# poker_shematics_2.net
KiCad netlist of a schematic drawn in Altium Designer
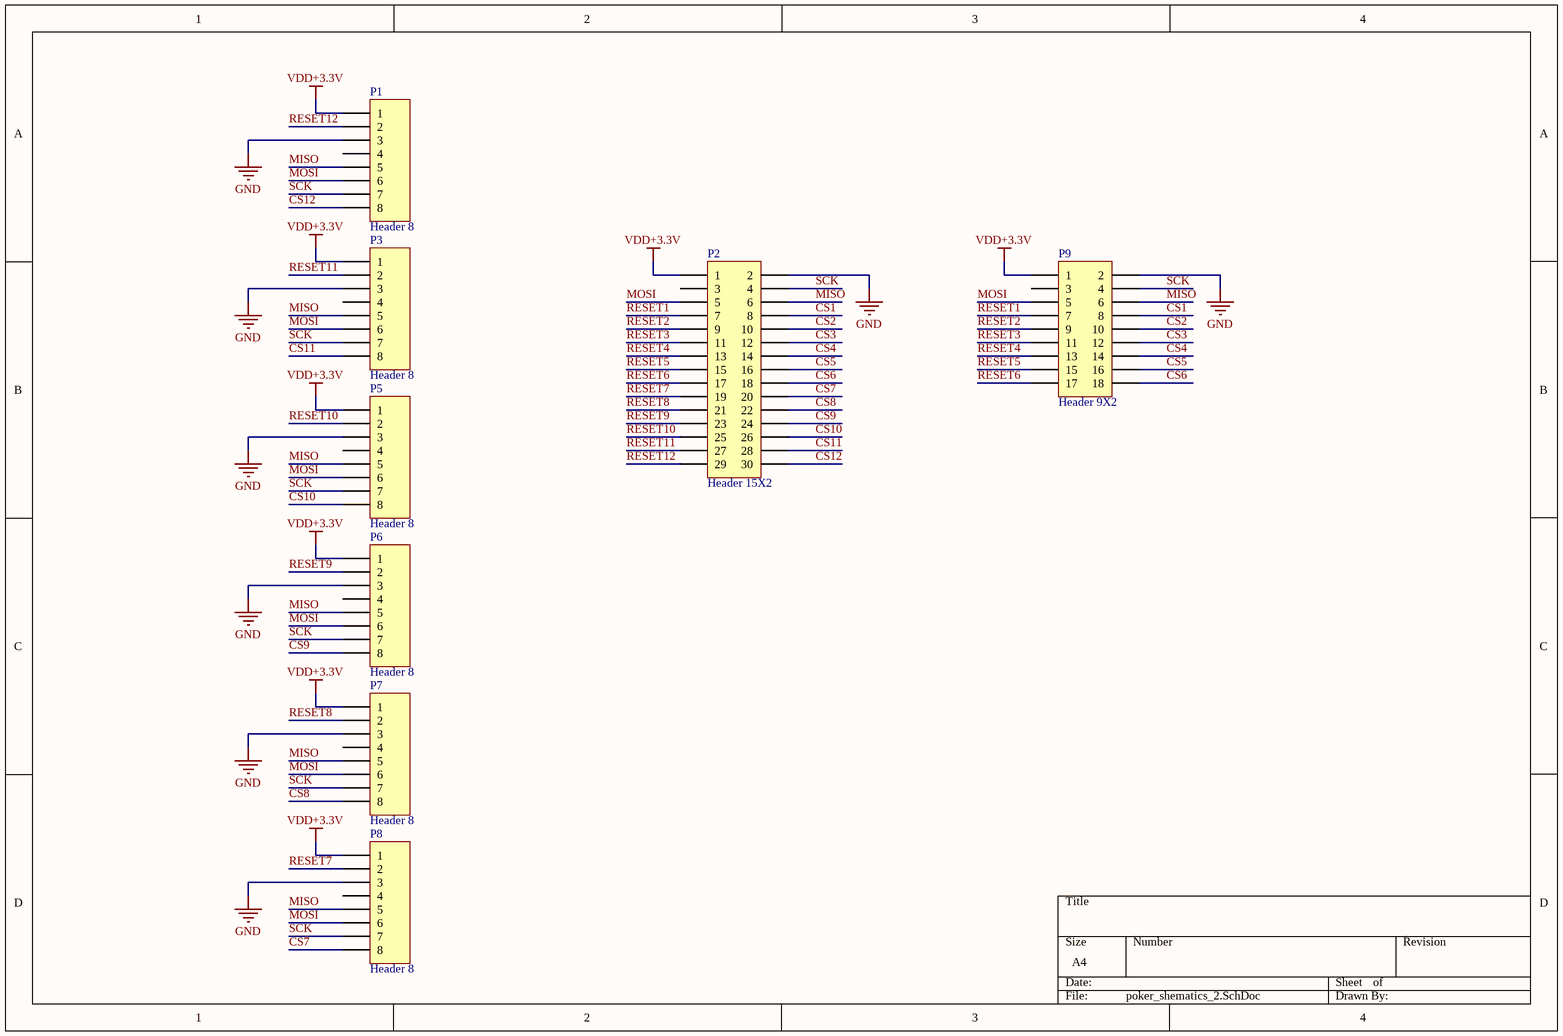
[diagram p0: poker_shematics_2.SchDoc]

(export (version "E")
  (design (tool "Eeschema 10.0.6"))
  (components
    (comp (ref "P1")
      (value "Header 8")
      (footprint "HDR1X8")
      (description "Header, 8-Pin")
      (fields (field (name "PUBLISHER") "Altium Limited"))
      (libsource (lib "Miscellaneous Connectors") (part "Header 8"))
    )
    (comp (ref "P2")
      (value "Header 15X2")
      (footprint "HDR2X15")
      (description "Header, 15-Pin, Dual row")
      (fields (field (name "PUBLISHER") "Altium Limited"))
      (libsource (lib "Miscellaneous Connectors") (part "Header 15X2"))
    )
    (comp (ref "P3")
      (value "Header 8")
      (footprint "HDR1X8")
      (description "Header, 8-Pin")
      (fields (field (name "PUBLISHER") "Altium Limited"))
      (libsource (lib "Miscellaneous Connectors") (part "Header 8"))
    )
    (comp (ref "P5")
      (value "Header 8")
      (footprint "HDR1X8")
      (description "Header, 8-Pin")
      (fields (field (name "PUBLISHER") "Altium Limited"))
      (libsource (lib "Miscellaneous Connectors") (part "Header 8"))
    )
    (comp (ref "P6")
      (value "Header 8")
      (footprint "HDR1X8")
      (description "Header, 8-Pin")
      (fields (field (name "PUBLISHER") "Altium Limited"))
      (libsource (lib "Miscellaneous Connectors") (part "Header 8"))
    )
    (comp (ref "P7")
      (value "Header 8")
      (footprint "HDR1X8")
      (description "Header, 8-Pin")
      (fields (field (name "PUBLISHER") "Altium Limited"))
      (libsource (lib "Miscellaneous Connectors") (part "Header 8"))
    )
    (comp (ref "P8")
      (value "Header 8")
      (footprint "HDR1X8")
      (description "Header, 8-Pin")
      (fields (field (name "PUBLISHER") "Altium Limited"))
      (libsource (lib "Miscellaneous Connectors") (part "Header 8"))
    )
    (comp (ref "P9")
      (value "Header 9X2")
      (footprint "HDR2X9")
      (description "Header, 9-Pin, Dual row")
      (fields (field (name "PUBLISHER") "Altium Limited"))
      (libsource (lib "Miscellaneous Connectors") (part "Header 9X2"))
    )
  )
  (nets
    (net (code "1") (name "/CS1") (class "Default")
      (node (ref "P2") (pin "8") (pinfunction "8_8") (pintype "passive"))
      (node (ref "P9") (pin "8") (pinfunction "8_8") (pintype "passive"))
    )
    (net (code "2") (name "/CS2") (class "Default")
      (node (ref "P2") (pin "10") (pinfunction "10_10") (pintype "passive"))
      (node (ref "P9") (pin "10") (pinfunction "10_10") (pintype "passive"))
    )
    (net (code "3") (name "/CS3") (class "Default")
      (node (ref "P2") (pin "12") (pinfunction "12_12") (pintype "passive"))
      (node (ref "P9") (pin "12") (pinfunction "12_12") (pintype "passive"))
    )
    (net (code "4") (name "/CS4") (class "Default")
      (node (ref "P2") (pin "14") (pinfunction "14_14") (pintype "passive"))
      (node (ref "P9") (pin "14") (pinfunction "14_14") (pintype "passive"))
    )
    (net (code "5") (name "/CS5") (class "Default")
      (node (ref "P2") (pin "16") (pinfunction "16_16") (pintype "passive"))
      (node (ref "P9") (pin "16") (pinfunction "16_16") (pintype "passive"))
    )
    (net (code "6") (name "/CS6") (class "Default")
      (node (ref "P2") (pin "18") (pinfunction "18_18") (pintype "passive"))
      (node (ref "P9") (pin "18") (pinfunction "18_18") (pintype "passive"))
    )
    (net (code "7") (name "/CS7") (class "Default")
      (node (ref "P2") (pin "20") (pinfunction "20_20") (pintype "passive"))
      (node (ref "P8") (pin "8") (pinfunction "8_8") (pintype "passive"))
    )
    (net (code "8") (name "/CS8") (class "Default")
      (node (ref "P2") (pin "22") (pinfunction "22_22") (pintype "passive"))
      (node (ref "P7") (pin "8") (pinfunction "8_8") (pintype "passive"))
    )
    (net (code "9") (name "/CS9") (class "Default")
      (node (ref "P2") (pin "24") (pinfunction "24_24") (pintype "passive"))
      (node (ref "P6") (pin "8") (pinfunction "8_8") (pintype "passive"))
    )
    (net (code "10") (name "/CS10") (class "Default")
      (node (ref "P2") (pin "26") (pinfunction "26_26") (pintype "passive"))
      (node (ref "P5") (pin "8") (pinfunction "8_8") (pintype "passive"))
    )
    (net (code "11") (name "/CS11") (class "Default")
      (node (ref "P2") (pin "28") (pinfunction "28_28") (pintype "passive"))
      (node (ref "P3") (pin "8") (pinfunction "8_8") (pintype "passive"))
    )
    (net (code "12") (name "/CS12") (class "Default")
      (node (ref "P1") (pin "8") (pinfunction "8_8") (pintype "passive"))
      (node (ref "P2") (pin "30") (pinfunction "30_30") (pintype "passive"))
    )
    (net (code "13") (name "/MISO") (class "Default")
      (node (ref "P1") (pin "5") (pinfunction "5_5") (pintype "passive"))
      (node (ref "P2") (pin "6") (pinfunction "6_6") (pintype "passive"))
      (node (ref "P3") (pin "5") (pinfunction "5_5") (pintype "passive"))
      (node (ref "P5") (pin "5") (pinfunction "5_5") (pintype "passive"))
      (node (ref "P6") (pin "5") (pinfunction "5_5") (pintype "passive"))
      (node (ref "P7") (pin "5") (pinfunction "5_5") (pintype "passive"))
      (node (ref "P8") (pin "5") (pinfunction "5_5") (pintype "passive"))
      (node (ref "P9") (pin "6") (pinfunction "6_6") (pintype "passive"))
    )
    (net (code "14") (name "/MOSI") (class "Default")
      (node (ref "P1") (pin "6") (pinfunction "6_6") (pintype "passive"))
      (node (ref "P2") (pin "5") (pinfunction "5_5") (pintype "passive"))
      (node (ref "P3") (pin "6") (pinfunction "6_6") (pintype "passive"))
      (node (ref "P5") (pin "6") (pinfunction "6_6") (pintype "passive"))
      (node (ref "P6") (pin "6") (pinfunction "6_6") (pintype "passive"))
      (node (ref "P7") (pin "6") (pinfunction "6_6") (pintype "passive"))
      (node (ref "P8") (pin "6") (pinfunction "6_6") (pintype "passive"))
      (node (ref "P9") (pin "5") (pinfunction "5_5") (pintype "passive"))
    )
    (net (code "15") (name "/RESET1") (class "Default")
      (node (ref "P2") (pin "7") (pinfunction "7_7") (pintype "passive"))
      (node (ref "P9") (pin "7") (pinfunction "7_7") (pintype "passive"))
    )
    (net (code "16") (name "/RESET2") (class "Default")
      (node (ref "P2") (pin "9") (pinfunction "9_9") (pintype "passive"))
      (node (ref "P9") (pin "9") (pinfunction "9_9") (pintype "passive"))
    )
    (net (code "17") (name "/RESET3") (class "Default")
      (node (ref "P2") (pin "11") (pinfunction "11_11") (pintype "passive"))
      (node (ref "P9") (pin "11") (pinfunction "11_11") (pintype "passive"))
    )
    (net (code "18") (name "/RESET4") (class "Default")
      (node (ref "P2") (pin "13") (pinfunction "13_13") (pintype "passive"))
      (node (ref "P9") (pin "13") (pinfunction "13_13") (pintype "passive"))
    )
    (net (code "19") (name "/RESET5") (class "Default")
      (node (ref "P2") (pin "15") (pinfunction "15_15") (pintype "passive"))
      (node (ref "P9") (pin "15") (pinfunction "15_15") (pintype "passive"))
    )
    (net (code "20") (name "/RESET6") (class "Default")
      (node (ref "P2") (pin "17") (pinfunction "17_17") (pintype "passive"))
      (node (ref "P9") (pin "17") (pinfunction "17_17") (pintype "passive"))
    )
    (net (code "21") (name "/RESET7") (class "Default")
      (node (ref "P2") (pin "19") (pinfunction "19_19") (pintype "passive"))
      (node (ref "P8") (pin "2") (pinfunction "2_2") (pintype "passive"))
    )
    (net (code "22") (name "/RESET8") (class "Default")
      (node (ref "P2") (pin "21") (pinfunction "21_21") (pintype "passive"))
      (node (ref "P7") (pin "2") (pinfunction "2_2") (pintype "passive"))
    )
    (net (code "23") (name "/RESET9") (class "Default")
      (node (ref "P2") (pin "23") (pinfunction "23_23") (pintype "passive"))
      (node (ref "P6") (pin "2") (pinfunction "2_2") (pintype "passive"))
    )
    (net (code "24") (name "/RESET10") (class "Default")
      (node (ref "P2") (pin "25") (pinfunction "25_25") (pintype "passive"))
      (node (ref "P5") (pin "2") (pinfunction "2_2") (pintype "passive"))
    )
    (net (code "25") (name "/RESET11") (class "Default")
      (node (ref "P2") (pin "27") (pinfunction "27_27") (pintype "passive"))
      (node (ref "P3") (pin "2") (pinfunction "2_2") (pintype "passive"))
    )
    (net (code "26") (name "/RESET12") (class "Default")
      (node (ref "P1") (pin "2") (pinfunction "2_2") (pintype "passive"))
      (node (ref "P2") (pin "29") (pinfunction "29_29") (pintype "passive"))
    )
    (net (code "27") (name "/SCK") (class "Default")
      (node (ref "P1") (pin "7") (pinfunction "7_7") (pintype "passive"))
      (node (ref "P2") (pin "4") (pinfunction "4_4") (pintype "passive"))
      (node (ref "P3") (pin "7") (pinfunction "7_7") (pintype "passive"))
      (node (ref "P5") (pin "7") (pinfunction "7_7") (pintype "passive"))
      (node (ref "P6") (pin "7") (pinfunction "7_7") (pintype "passive"))
      (node (ref "P7") (pin "7") (pinfunction "7_7") (pintype "passive"))
      (node (ref "P8") (pin "7") (pinfunction "7_7") (pintype "passive"))
      (node (ref "P9") (pin "4") (pinfunction "4_4") (pintype "passive"))
    )
    (net (code "28") (name "GND") (class "Default")
      (node (ref "P1") (pin "3") (pinfunction "3_3") (pintype "passive"))
      (node (ref "P2") (pin "2") (pinfunction "2_2") (pintype "passive"))
      (node (ref "P3") (pin "3") (pinfunction "3_3") (pintype "passive"))
      (node (ref "P5") (pin "3") (pinfunction "3_3") (pintype "passive"))
      (node (ref "P6") (pin "3") (pinfunction "3_3") (pintype "passive"))
      (node (ref "P7") (pin "3") (pinfunction "3_3") (pintype "passive"))
      (node (ref "P8") (pin "3") (pinfunction "3_3") (pintype "passive"))
      (node (ref "P9") (pin "2") (pinfunction "2_2") (pintype "passive"))
    )
    (net (code "29") (name "VDD+3.3V") (class "Default")
      (node (ref "P1") (pin "1") (pinfunction "1_1") (pintype "passive"))
      (node (ref "P2") (pin "1") (pinfunction "1_1") (pintype "passive"))
      (node (ref "P3") (pin "1") (pinfunction "1_1") (pintype "passive"))
      (node (ref "P5") (pin "1") (pinfunction "1_1") (pintype "passive"))
      (node (ref "P6") (pin "1") (pinfunction "1_1") (pintype "passive"))
      (node (ref "P7") (pin "1") (pinfunction "1_1") (pintype "passive"))
      (node (ref "P8") (pin "1") (pinfunction "1_1") (pintype "passive"))
      (node (ref "P9") (pin "1") (pinfunction "1_1") (pintype "passive"))
    )
    (net (code "30") (name "unconnected-(P1-Pad4)") (class "Default")
      (node (ref "P1") (pin "4") (pinfunction "4_4") (pintype "passive"))
    )
    (net (code "31") (name "unconnected-(P2-Pad3)") (class "Default")
      (node (ref "P2") (pin "3") (pinfunction "3_3") (pintype "passive"))
    )
    (net (code "32") (name "unconnected-(P3-Pad4)") (class "Default")
      (node (ref "P3") (pin "4") (pinfunction "4_4") (pintype "passive"))
    )
    (net (code "33") (name "unconnected-(P5-Pad4)") (class "Default")
      (node (ref "P5") (pin "4") (pinfunction "4_4") (pintype "passive"))
    )
    (net (code "34") (name "unconnected-(P6-Pad4)") (class "Default")
      (node (ref "P6") (pin "4") (pinfunction "4_4") (pintype "passive"))
    )
    (net (code "35") (name "unconnected-(P7-Pad4)") (class "Default")
      (node (ref "P7") (pin "4") (pinfunction "4_4") (pintype "passive"))
    )
    (net (code "36") (name "unconnected-(P8-Pad4)") (class "Default")
      (node (ref "P8") (pin "4") (pinfunction "4_4") (pintype "passive"))
    )
    (net (code "37") (name "unconnected-(P9-Pad3)") (class "Default")
      (node (ref "P9") (pin "3") (pinfunction "3_3") (pintype "passive"))
    )
  )
)
